# RS485_M_V1.net
KiCad netlist of a schematic drawn in Altium Designer
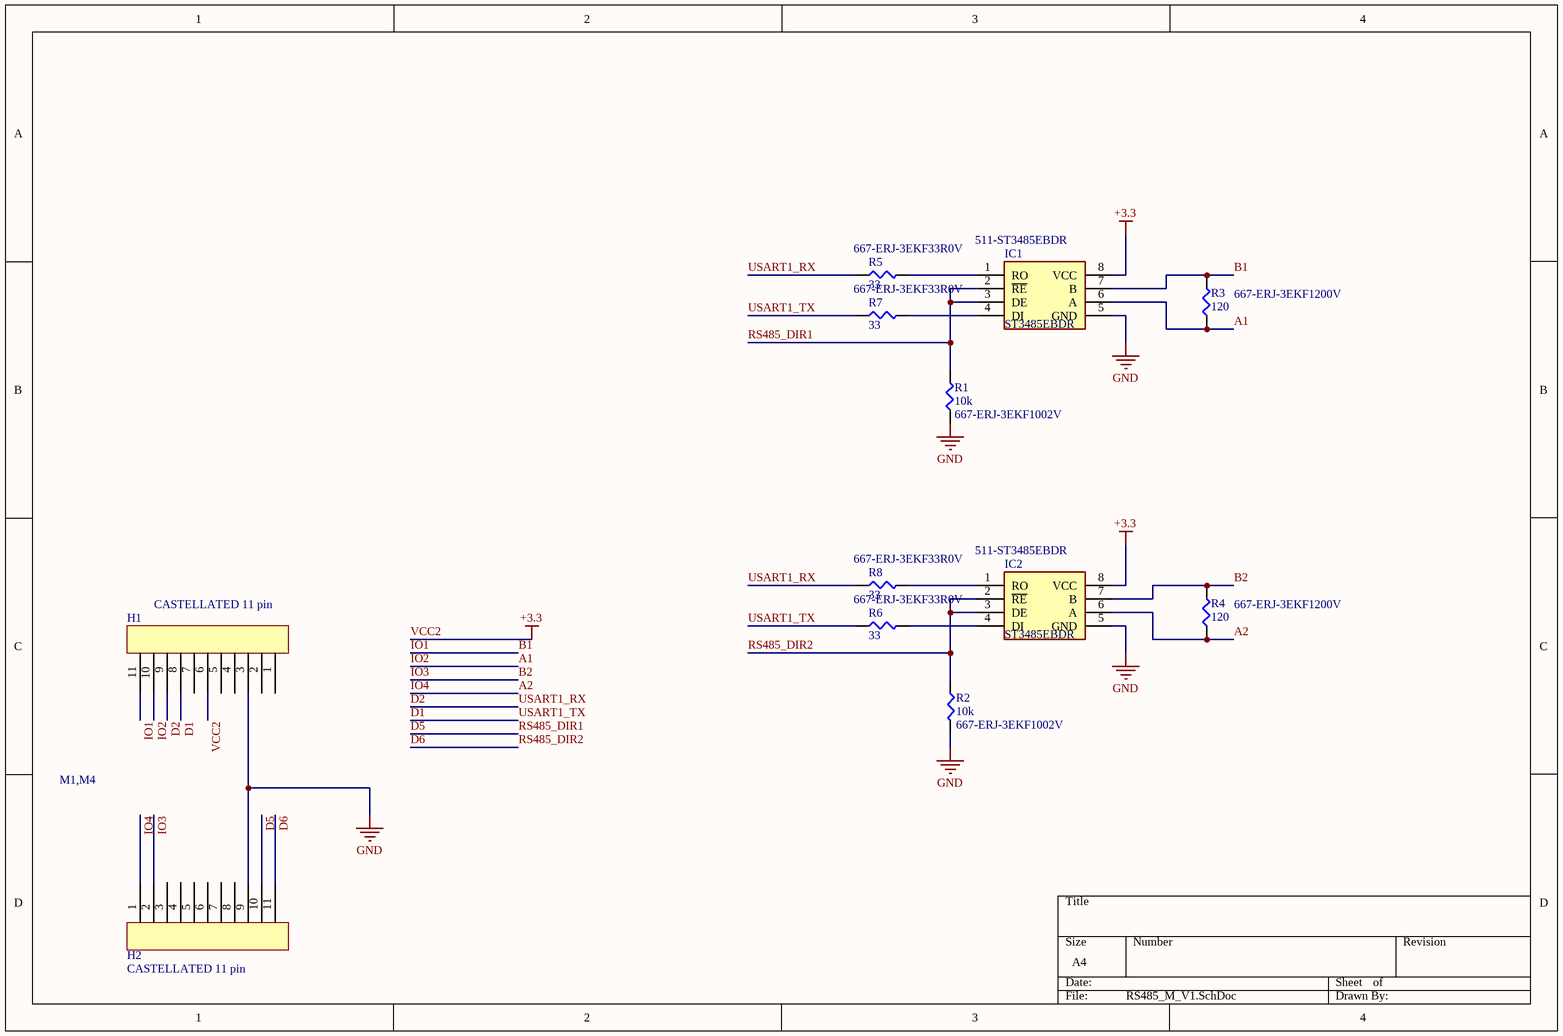
[diagram p0: RS485_M_V1.SchDoc]

(export (version "E")
  (design (tool "Eeschema 10.0.6"))
  (components
    (comp (ref "H1")
      (value "CASTELLATED 11 pin")
      (footprint "CASTELLATED 11 pin")
      (libsource (lib "") (part "CASTELLATED 11 pin_1"))
    )
    (comp (ref "H2")
      (value "CASTELLATED 11 pin")
      (footprint "CASTELLATED 11 pin")
      (libsource (lib "USIB") (part "CASTELLATED 11 pin"))
    )
    (comp (ref "IC1")
      (value "ST3485EBDR")
      (footprint "SamacSys:SOIC127P600X175-8N")
      (description "Integrated Circuit")
      (fields
        (field (name "MOUSER2 PART NUMBER") "511-ST3485EBDR")
        (field (name "SUPPLIER PART NUMBER 1") "511-ST3485EBDR")
      )
      (libsource (lib "*") (part "ST3485EBDR"))
    )
    (comp (ref "IC2")
      (value "ST3485EBDR")
      (footprint "SamacSys:SOIC127P600X175-8N")
      (description "Integrated Circuit")
      (fields
        (field (name "MOUSER2 PART NUMBER") "511-ST3485EBDR")
        (field (name "SUPPLIER PART NUMBER 1") "511-ST3485EBDR")
      )
      (libsource (lib "*") (part "ST3485EBDR"))
    )
    (comp (ref "R1")
      (value "10k")
      (footprint "SMD-0603-RES")
      (description "RES SMD 10K OHM 1% 1/10W 0603")
      (fields
        (field (name "PART NUMBER") "ERJ-3EKF1002V")
        (field (name "DIGI-KEY PART NUMBER") "P10.0KHCT-ND")
        (field (name "SUPPLIER PART NUMBER 1") "667-ERJ-3EKF1002V")
      )
      (libsource (lib "Panasonic_ERJ_0603") (part "ERJ-3EKF1002V"))
    )
    (comp (ref "R2")
      (value "10k")
      (footprint "SMD-0603-RES")
      (description "RES SMD 10K OHM 1% 1/10W 0603")
      (fields
        (field (name "PART NUMBER") "ERJ-3EKF1002V")
        (field (name "DIGI-KEY PART NUMBER") "P10.0KHCT-ND")
        (field (name "SUPPLIER PART NUMBER 1") "667-ERJ-3EKF1002V")
      )
      (libsource (lib "Panasonic_ERJ_0603") (part "ERJ-3EKF1002V"))
    )
    (comp (ref "R3")
      (value "120")
      (footprint "SMD-0603-RES")
      (description "RES SMD 120 OHM 1% 1/10W 0603")
      (fields
        (field (name "PART NUMBER") "ERJ-3EKF1200V")
        (field (name "DIGI-KEY PART NUMBER") "P120HCT-ND")
        (field (name "SUPPLIER PART NUMBER 1") "667-ERJ-3EKF1200V")
      )
      (libsource (lib "Panasonic_ERJ_0603") (part "ERJ-3EKF1200V"))
    )
    (comp (ref "R4")
      (value "120")
      (footprint "SMD-0603-RES")
      (description "RES SMD 120 OHM 1% 1/10W 0603")
      (fields
        (field (name "PART NUMBER") "ERJ-3EKF1200V")
        (field (name "DIGI-KEY PART NUMBER") "P120HCT-ND")
        (field (name "SUPPLIER PART NUMBER 1") "667-ERJ-3EKF1200V")
      )
      (libsource (lib "Panasonic_ERJ_0603") (part "ERJ-3EKF1200V"))
    )
    (comp (ref "R5")
      (value "33")
      (footprint "SMD-0603-RES")
      (description "RES SMD 33 OHM 1% 1/10W 0603")
      (fields
        (field (name "PART NUMBER") "ERJ-3EKF33R0V")
        (field (name "DIGI-KEY PART NUMBER") "P33.0HCT-ND")
        (field (name "SUPPLIER PART NUMBER 1") "667-ERJ-3EKF33R0V")
      )
      (libsource (lib "Panasonic_ERJ_0603") (part "ERJ-3EKF33R0V"))
    )
    (comp (ref "R6")
      (value "33")
      (footprint "SMD-0603-RES")
      (description "RES SMD 33 OHM 1% 1/10W 0603")
      (fields
        (field (name "PART NUMBER") "ERJ-3EKF33R0V")
        (field (name "DIGI-KEY PART NUMBER") "P33.0HCT-ND")
        (field (name "SUPPLIER PART NUMBER 1") "667-ERJ-3EKF33R0V")
      )
      (libsource (lib "Panasonic_ERJ_0603") (part "ERJ-3EKF33R0V"))
    )
    (comp (ref "R7")
      (value "33")
      (footprint "SMD-0603-RES")
      (description "RES SMD 33 OHM 1% 1/10W 0603")
      (fields
        (field (name "PART NUMBER") "ERJ-3EKF33R0V")
        (field (name "DIGI-KEY PART NUMBER") "P33.0HCT-ND")
        (field (name "SUPPLIER PART NUMBER 1") "667-ERJ-3EKF33R0V")
      )
      (libsource (lib "Panasonic_ERJ_0603") (part "ERJ-3EKF33R0V"))
    )
    (comp (ref "R8")
      (value "33")
      (footprint "SMD-0603-RES")
      (description "RES SMD 33 OHM 1% 1/10W 0603")
      (fields
        (field (name "PART NUMBER") "ERJ-3EKF33R0V")
        (field (name "DIGI-KEY PART NUMBER") "P33.0HCT-ND")
        (field (name "SUPPLIER PART NUMBER 1") "667-ERJ-3EKF33R0V")
      )
      (libsource (lib "Panasonic_ERJ_0603") (part "ERJ-3EKF33R0V"))
    )
  )
  (nets
    (net (code "1") (name "+3.3") (class "Default")
      (node (ref "H1") (pin "6") (pintype "passive"))
      (node (ref "IC1") (pin "8") (pinfunction "VCC_8") (pintype "passive"))
      (node (ref "IC2") (pin "8") (pinfunction "VCC_8") (pintype "passive"))
    )
    (net (code "2") (name "/A1") (class "Default")
      (node (ref "H1") (pin "10") (pintype "passive"))
      (node (ref "IC1") (pin "6") (pinfunction "A_6") (pintype "passive"))
      (node (ref "R3") (pin "1") (pinfunction "1_1") (pintype "passive"))
    )
    (net (code "3") (name "/A2") (class "Default")
      (node (ref "H2") (pin "1") (pintype "passive"))
      (node (ref "IC2") (pin "6") (pinfunction "A_6") (pintype "passive"))
      (node (ref "R4") (pin "1") (pinfunction "1_1") (pintype "passive"))
    )
    (net (code "4") (name "/B1") (class "Default")
      (node (ref "H1") (pin "11") (pintype "passive"))
      (node (ref "IC1") (pin "7") (pinfunction "B_7") (pintype "passive"))
      (node (ref "R3") (pin "2") (pinfunction "2_2") (pintype "passive"))
    )
    (net (code "5") (name "/B2") (class "Default")
      (node (ref "H2") (pin "2") (pintype "passive"))
      (node (ref "IC2") (pin "7") (pinfunction "B_7") (pintype "passive"))
      (node (ref "R4") (pin "2") (pinfunction "2_2") (pintype "passive"))
    )
    (net (code "6") (name "/D1") (class "Default")
      (node (ref "H1") (pin "8") (pintype "passive"))
      (node (ref "R6") (pin "1") (pinfunction "1_1") (pintype "passive"))
      (node (ref "R7") (pin "1") (pinfunction "1_1") (pintype "passive"))
    )
    (net (code "7") (name "/D2") (class "Default")
      (node (ref "H1") (pin "9") (pintype "passive"))
      (node (ref "R5") (pin "1") (pinfunction "1_1") (pintype "passive"))
      (node (ref "R8") (pin "1") (pinfunction "1_1") (pintype "passive"))
    )
    (net (code "8") (name "/D5") (class "Default")
      (node (ref "H2") (pin "10") (pintype "passive"))
      (node (ref "IC1") (pin "2") (pinfunction "~{RE}_2") (pintype "passive"))
      (node (ref "IC1") (pin "3") (pinfunction "DE_3") (pintype "passive"))
      (node (ref "R1") (pin "2") (pinfunction "2_2") (pintype "passive"))
    )
    (net (code "9") (name "/D6") (class "Default")
      (node (ref "H2") (pin "11") (pintype "passive"))
      (node (ref "IC2") (pin "2") (pinfunction "~{RE}_2") (pintype "passive"))
      (node (ref "IC2") (pin "3") (pinfunction "DE_3") (pintype "passive"))
      (node (ref "R2") (pin "1") (pinfunction "1_1") (pintype "passive"))
    )
    (net (code "10") (name "GND") (class "Default")
      (node (ref "H1") (pin "3") (pintype "passive"))
      (node (ref "H2") (pin "9") (pintype "passive"))
      (node (ref "IC1") (pin "5") (pinfunction "GND_5") (pintype "passive"))
      (node (ref "IC2") (pin "5") (pinfunction "GND_5") (pintype "passive"))
      (node (ref "R1") (pin "1") (pinfunction "1_1") (pintype "passive"))
      (node (ref "R2") (pin "2") (pinfunction "2_2") (pintype "passive"))
    )
    (net (code "11") (name "Net-(IC1-DI)") (class "Default")
      (node (ref "IC1") (pin "4") (pinfunction "DI_4") (pintype "passive"))
      (node (ref "R7") (pin "2") (pinfunction "2_2") (pintype "passive"))
    )
    (net (code "12") (name "Net-(IC1-RO)") (class "Default")
      (node (ref "IC1") (pin "1") (pinfunction "RO_1") (pintype "passive"))
      (node (ref "R5") (pin "2") (pinfunction "2_2") (pintype "passive"))
    )
    (net (code "13") (name "Net-(IC2-DI)") (class "Default")
      (node (ref "IC2") (pin "4") (pinfunction "DI_4") (pintype "passive"))
      (node (ref "R6") (pin "2") (pinfunction "2_2") (pintype "passive"))
    )
    (net (code "14") (name "Net-(IC2-RO)") (class "Default")
      (node (ref "IC2") (pin "1") (pinfunction "RO_1") (pintype "passive"))
      (node (ref "R8") (pin "2") (pinfunction "2_2") (pintype "passive"))
    )
    (net (code "15") (name "unconnected-(H1-Pad1)") (class "Default")
      (node (ref "H1") (pin "1") (pintype "passive"))
    )
    (net (code "16") (name "unconnected-(H1-Pad2)") (class "Default")
      (node (ref "H1") (pin "2") (pintype "passive"))
    )
    (net (code "17") (name "unconnected-(H1-Pad4)") (class "Default")
      (node (ref "H1") (pin "4") (pintype "passive"))
    )
    (net (code "18") (name "unconnected-(H1-Pad5)") (class "Default")
      (node (ref "H1") (pin "5") (pintype "passive"))
    )
    (net (code "19") (name "unconnected-(H1-Pad7)") (class "Default")
      (node (ref "H1") (pin "7") (pintype "passive"))
    )
    (net (code "20") (name "unconnected-(H2-Pad3)") (class "Default")
      (node (ref "H2") (pin "3") (pintype "passive"))
    )
    (net (code "21") (name "unconnected-(H2-Pad4)") (class "Default")
      (node (ref "H2") (pin "4") (pintype "passive"))
    )
    (net (code "22") (name "unconnected-(H2-Pad5)") (class "Default")
      (node (ref "H2") (pin "5") (pintype "passive"))
    )
    (net (code "23") (name "unconnected-(H2-Pad6)") (class "Default")
      (node (ref "H2") (pin "6") (pintype "passive"))
    )
    (net (code "24") (name "unconnected-(H2-Pad7)") (class "Default")
      (node (ref "H2") (pin "7") (pintype "passive"))
    )
    (net (code "25") (name "unconnected-(H2-Pad8)") (class "Default")
      (node (ref "H2") (pin "8") (pintype "passive"))
    )
  )
)
